# teensyMotors01.net
KiCad netlist of a schematic drawn in EAGLE
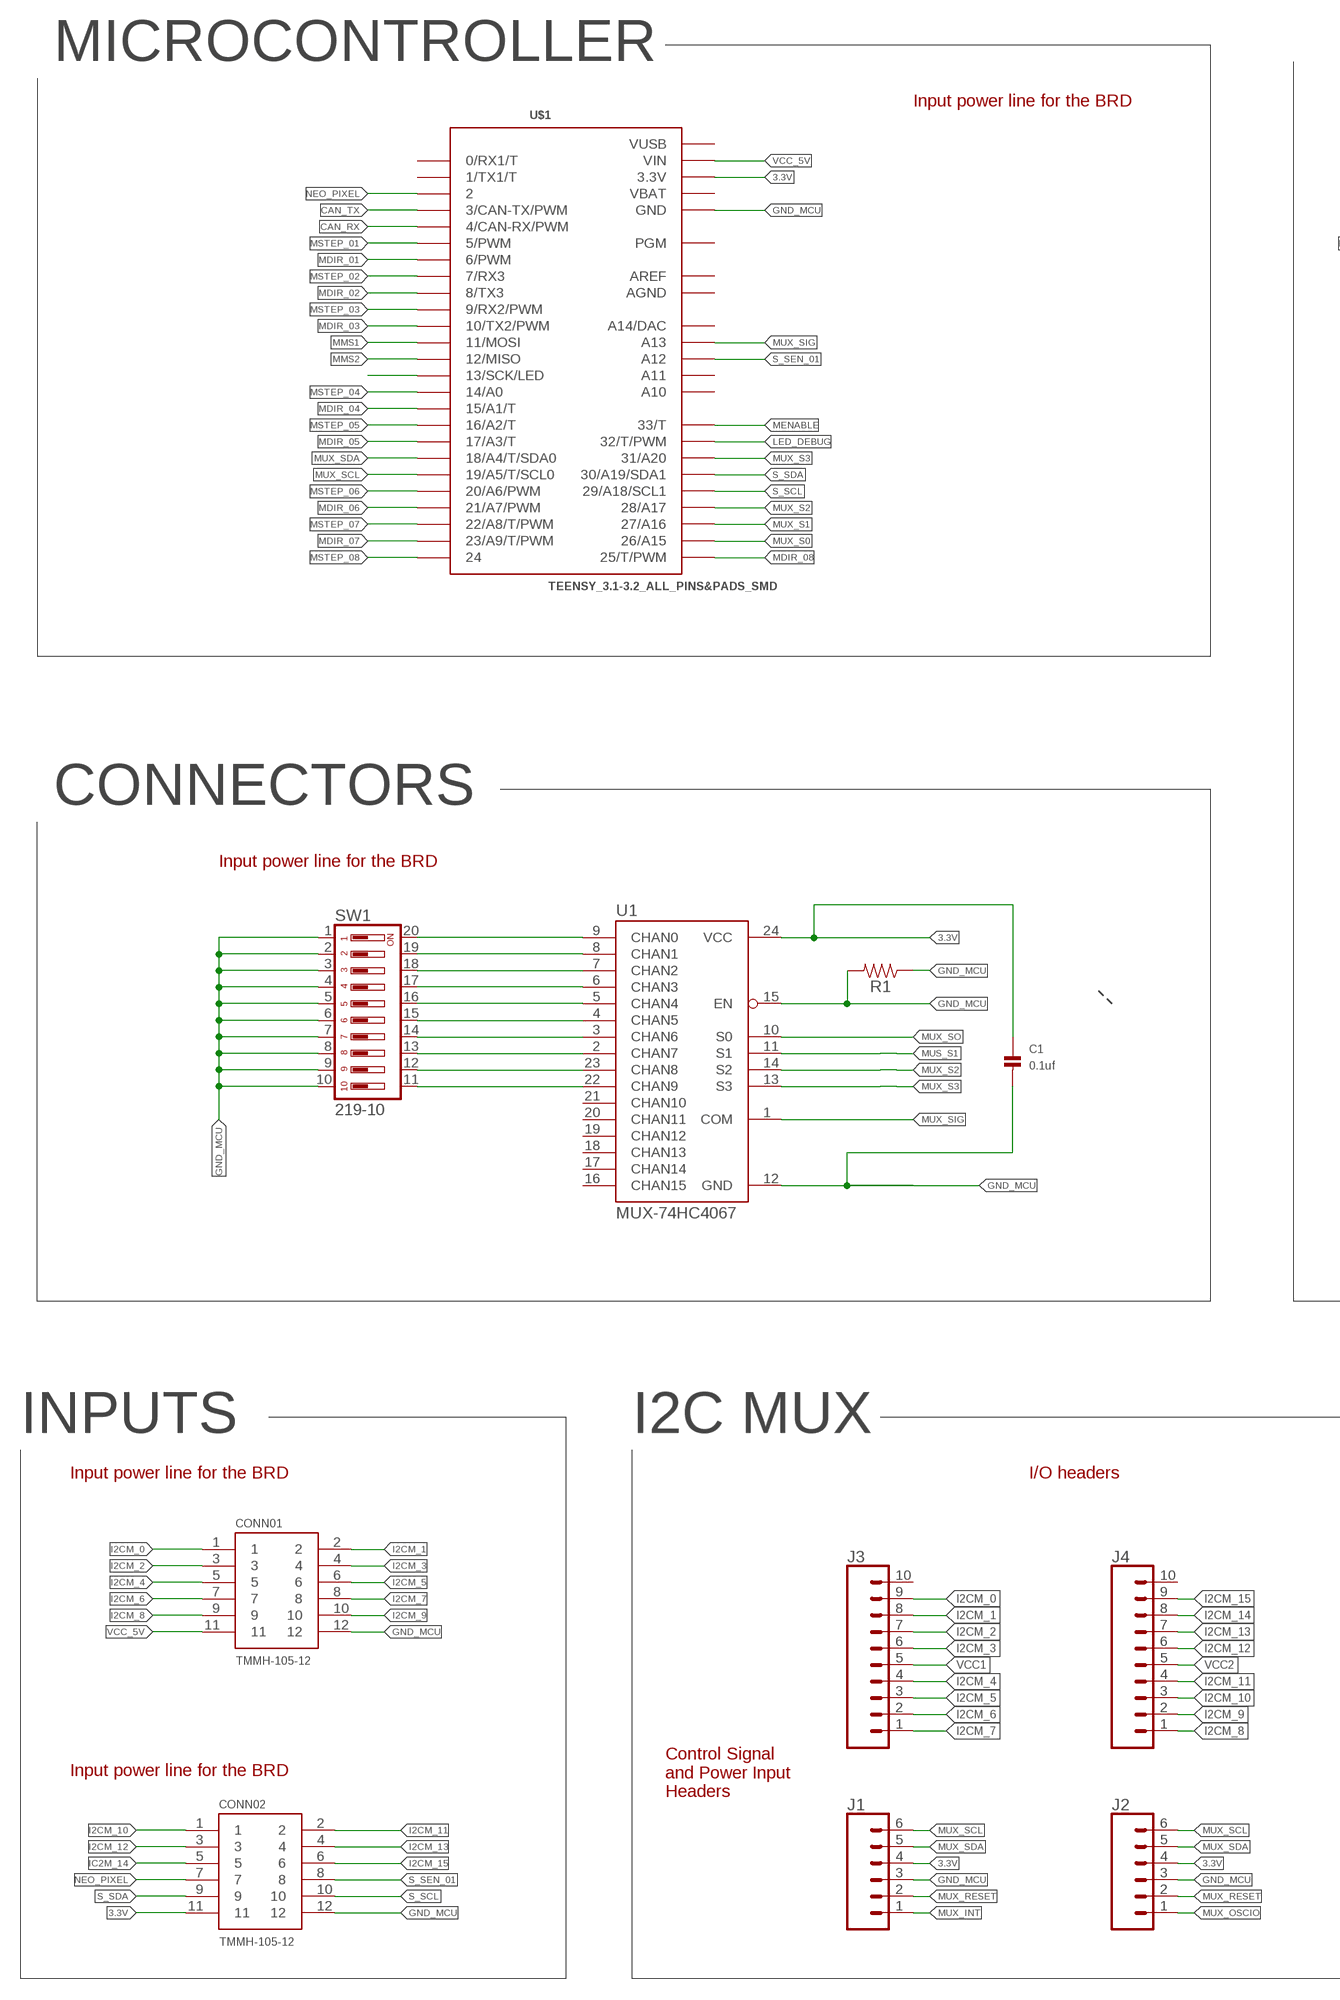
[diagram p0: schematic, sheet 1, part 1 of 2]
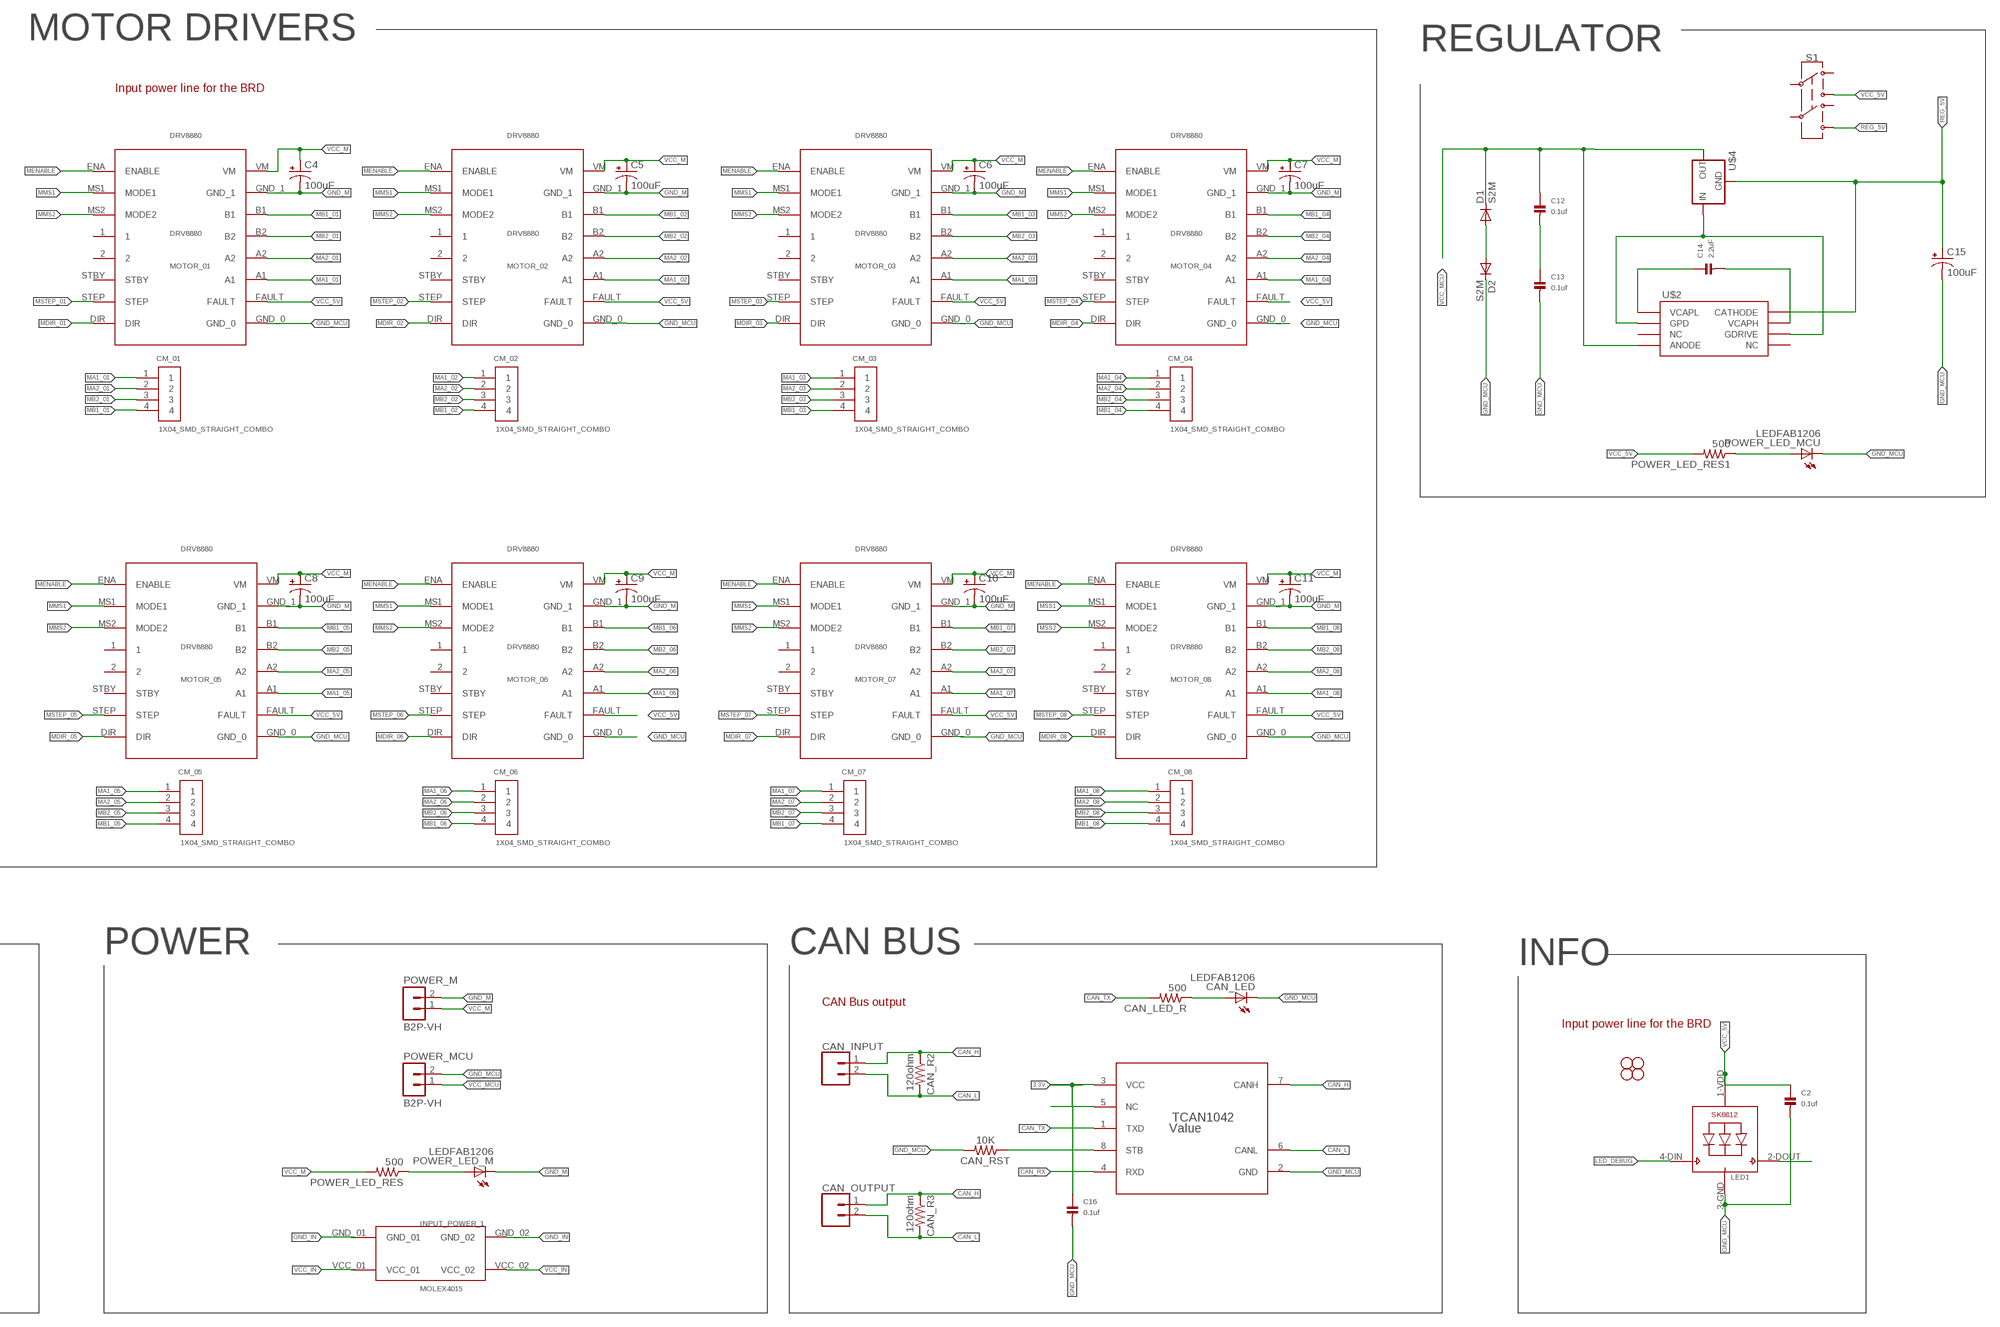
[diagram p1: schematic, sheet 1, part 2 of 2]

(export (version "E")
  (design (tool "Eeschema 10.0.6"))
  (components
    (comp (ref "C1")
      (value "0.1uf")
      (footprint "eagle-import:1206")
      (libsource (lib "eagle-import") (part "CAP_CERAMIC1206"))
    )
    (comp (ref "C2")
      (value "0.1uf")
      (footprint "eagle-import:1206")
      (libsource (lib "eagle-import") (part "CAP_CERAMIC1206"))
    )
    (comp (ref "C4")
      (value "100uF")
      (footprint "eagle-import:PANASONIC_D")
      (libsource (lib "eagle-import") (part "100UF-POLAR-25V-20%(ELEC)"))
    )
    (comp (ref "C5")
      (value "100uF")
      (footprint "eagle-import:PANASONIC_D")
      (libsource (lib "eagle-import") (part "100UF-POLAR-25V-20%(ELEC)"))
    )
    (comp (ref "C6")
      (value "100uF")
      (footprint "eagle-import:PANASONIC_D")
      (libsource (lib "eagle-import") (part "100UF-POLAR-25V-20%(ELEC)"))
    )
    (comp (ref "C7")
      (value "100uF")
      (footprint "eagle-import:PANASONIC_D")
      (libsource (lib "eagle-import") (part "100UF-POLAR-25V-20%(ELEC)"))
    )
    (comp (ref "C8")
      (value "100uF")
      (footprint "eagle-import:PANASONIC_D")
      (libsource (lib "eagle-import") (part "100UF-POLAR-25V-20%(ELEC)"))
    )
    (comp (ref "C9")
      (value "100uF")
      (footprint "eagle-import:PANASONIC_D")
      (libsource (lib "eagle-import") (part "100UF-POLAR-25V-20%(ELEC)"))
    )
    (comp (ref "C10")
      (value "100uF")
      (footprint "eagle-import:PANASONIC_D")
      (libsource (lib "eagle-import") (part "100UF-POLAR-25V-20%(ELEC)"))
    )
    (comp (ref "C11")
      (value "100uF")
      (footprint "eagle-import:PANASONIC_D")
      (libsource (lib "eagle-import") (part "100UF-POLAR-25V-20%(ELEC)"))
    )
    (comp (ref "C12")
      (value "0.1uf")
      (footprint "eagle-import:1206")
      (libsource (lib "eagle-import") (part "CAP_CERAMIC1206"))
    )
    (comp (ref "C13")
      (value "0.1uf")
      (footprint "eagle-import:1206")
      (libsource (lib "eagle-import") (part "CAP_CERAMIC1206"))
    )
    (comp (ref "C14")
      (value "2.2uF")
      (footprint "eagle-import:1206")
      (libsource (lib "eagle-import") (part "CAP_CERAMIC1206"))
    )
    (comp (ref "C15")
      (value "100uF")
      (footprint "eagle-import:PANASONIC_D")
      (libsource (lib "eagle-import") (part "100UF-POLAR-25V-20%(ELEC)"))
    )
    (comp (ref "C16")
      (value "0.1uf")
      (footprint "eagle-import:1206")
      (libsource (lib "eagle-import") (part "CAP_CERAMIC1206"))
    )
    (comp (ref "CAN_INPUT")
      (value "CONN_02-JST-2MM-SMT")
      (footprint "eagle-import:JST-2-SMD")
      (libsource (lib "eagle-import") (part "CONN_02-JST-2MM-SMT"))
    )
    (comp (ref "CAN_LED")
      (value "LEDFAB1206")
      (footprint "eagle-import:LED1206FAB")
      (libsource (lib "eagle-import") (part "LEDFAB1206"))
    )
    (comp (ref "CAN_LED_R")
      (value "500")
      (footprint "eagle-import:R1206FAB")
      (libsource (lib "eagle-import") (part "RES-US1206FAB"))
    )
    (comp (ref "CAN_OUTPUT")
      (value "CONN_02-JST-2MM-SMT")
      (footprint "eagle-import:JST-2-SMD")
      (libsource (lib "eagle-import") (part "CONN_02-JST-2MM-SMT"))
    )
    (comp (ref "CAN_R2")
      (value "120ohm")
      (footprint "eagle-import:1206")
      (libsource (lib "eagle-import") (part "RESISTOR1206"))
    )
    (comp (ref "CAN_R3")
      (value "120ohm")
      (footprint "eagle-import:1206")
      (libsource (lib "eagle-import") (part "RESISTOR1206"))
    )
    (comp (ref "CAN_RST")
      (value "10K")
      (footprint "eagle-import:1206")
      (libsource (lib "eagle-import") (part "RESISTOR1206"))
    )
    (comp (ref "CM_01")
      (value "1X04_SMD_STRAIGHT_COMBO")
      (footprint "eagle-import:1X04-CLEANBIG")
      (libsource (lib "eagle-import") (part "1X4-CLEANBIG"))
    )
    (comp (ref "CM_02")
      (value "1X04_SMD_STRAIGHT_COMBO")
      (footprint "eagle-import:1X04-CLEANBIG")
      (libsource (lib "eagle-import") (part "1X4-CLEANBIG"))
    )
    (comp (ref "CM_03")
      (value "1X04_SMD_STRAIGHT_COMBO")
      (footprint "eagle-import:1X04-CLEANBIG")
      (libsource (lib "eagle-import") (part "1X4-CLEANBIG"))
    )
    (comp (ref "CM_04")
      (value "1X04_SMD_STRAIGHT_COMBO")
      (footprint "eagle-import:1X04-CLEANBIG")
      (libsource (lib "eagle-import") (part "1X4-CLEANBIG"))
    )
    (comp (ref "CM_05")
      (value "1X04_SMD_STRAIGHT_COMBO")
      (footprint "eagle-import:1X04-CLEANBIG")
      (libsource (lib "eagle-import") (part "1X4-CLEANBIG"))
    )
    (comp (ref "CM_06")
      (value "1X04_SMD_STRAIGHT_COMBO")
      (footprint "eagle-import:1X04-CLEANBIG")
      (libsource (lib "eagle-import") (part "1X4-CLEANBIG"))
    )
    (comp (ref "CM_07")
      (value "1X04_SMD_STRAIGHT_COMBO")
      (footprint "eagle-import:1X04-CLEANBIG")
      (libsource (lib "eagle-import") (part "1X4-CLEANBIG"))
    )
    (comp (ref "CM_08")
      (value "1X04_SMD_STRAIGHT_COMBO")
      (footprint "eagle-import:1X04-CLEANBIG")
      (libsource (lib "eagle-import") (part "1X4-CLEANBIG"))
    )
    (comp (ref "CONN01")
      (value "TMMH-105-12")
      (footprint "eagle-import:TMMH-105-12")
      (libsource (lib "eagle-import") (part "TMMH-105-12"))
    )
    (comp (ref "CONN02")
      (value "TMMH-105-12")
      (footprint "eagle-import:TMMH-105-12")
      (libsource (lib "eagle-import") (part "TMMH-105-12"))
    )
    (comp (ref "D1")
      (value "S2M")
      (footprint "eagle-import:DO214AA")
      (fields (field (name "MF") "Fairchild"))
      (libsource (lib "eagle-import") (part "S2M"))
    )
    (comp (ref "D2")
      (value "S2M")
      (footprint "eagle-import:DO214AA")
      (fields (field (name "MF") "Fairchild"))
      (libsource (lib "eagle-import") (part "S2M"))
    )
    (comp (ref "INPUT_POWER_1")
      (value "MOLEX4015")
      (footprint "eagle-import:MOLEX4015")
      (libsource (lib "eagle-import") (part "MOLEX4015"))
    )
    (comp (ref "J1")
      (value "CONN_06SMD_MALE")
      (footprint "eagle-import:1X06_SMD_MALE")
      (libsource (lib "eagle-import") (part "CONN_06SMD_MALE"))
    )
    (comp (ref "J2")
      (value "CONN_06SMD_MALE")
      (footprint "eagle-import:1X06_SMD_MALE")
      (libsource (lib "eagle-import") (part "CONN_06SMD_MALE"))
    )
    (comp (ref "J3")
      (value "CONN_10SMD_MALE")
      (footprint "eagle-import:1X10_SMD_MALE")
      (libsource (lib "eagle-import") (part "CONN_10SMD_MALE"))
    )
    (comp (ref "J4")
      (value "CONN_10SMD_MALE")
      (footprint "eagle-import:1X10_SMD_MALE")
      (libsource (lib "eagle-import") (part "CONN_10SMD_MALE"))
    )
    (comp (ref "LED1")
      (value "SK6812_5050N")
      (footprint "eagle-import:LED5050_N")
      (libsource (lib "eagle-import") (part "SK6812_5050N"))
    )
    (comp (ref "MOTOR_01")
      (value "DRV8880")
      (footprint "eagle-import:DRV8880")
      (libsource (lib "eagle-import") (part "DRV8880"))
    )
    (comp (ref "MOTOR_02")
      (value "DRV8880")
      (footprint "eagle-import:DRV8880")
      (libsource (lib "eagle-import") (part "DRV8880"))
    )
    (comp (ref "MOTOR_03")
      (value "DRV8880")
      (footprint "eagle-import:DRV8880")
      (libsource (lib "eagle-import") (part "DRV8880"))
    )
    (comp (ref "MOTOR_04")
      (value "DRV8880")
      (footprint "eagle-import:DRV8880")
      (libsource (lib "eagle-import") (part "DRV8880"))
    )
    (comp (ref "MOTOR_05")
      (value "DRV8880")
      (footprint "eagle-import:DRV8880")
      (libsource (lib "eagle-import") (part "DRV8880"))
    )
    (comp (ref "MOTOR_06")
      (value "DRV8880")
      (footprint "eagle-import:DRV8880")
      (libsource (lib "eagle-import") (part "DRV8880"))
    )
    (comp (ref "MOTOR_07")
      (value "DRV8880")
      (footprint "eagle-import:DRV8880")
      (libsource (lib "eagle-import") (part "DRV8880"))
    )
    (comp (ref "MOTOR_08")
      (value "DRV8880")
      (footprint "eagle-import:DRV8880")
      (libsource (lib "eagle-import") (part "DRV8880"))
    )
    (comp (ref "POWER_LED_M")
      (value "LEDFAB1206")
      (footprint "eagle-import:LED1206FAB")
      (libsource (lib "eagle-import") (part "LEDFAB1206"))
    )
    (comp (ref "POWER_LED_MCU")
      (value "LEDFAB1206")
      (footprint "eagle-import:LED1206FAB")
      (libsource (lib "eagle-import") (part "LEDFAB1206"))
    )
    (comp (ref "POWER_LED_RES")
      (value "500")
      (footprint "eagle-import:R1206FAB")
      (libsource (lib "eagle-import") (part "RES-US1206FAB"))
    )
    (comp (ref "POWER_LED_RES1")
      (value "500")
      (footprint "eagle-import:R1206FAB")
      (libsource (lib "eagle-import") (part "RES-US1206FAB"))
    )
    (comp (ref "POWER_M")
      (value "B2P-VH")
      (footprint "eagle-import:B2P-VH")
      (libsource (lib "eagle-import") (part "B2P-VH"))
    )
    (comp (ref "POWER_MCU")
      (value "B2P-VH")
      (footprint "eagle-import:B2P-VH")
      (libsource (lib "eagle-import") (part "B2P-VH"))
    )
    (comp (ref "R1")
      (value "RESISTOR1206")
      (footprint "eagle-import:1206")
      (libsource (lib "eagle-import") (part "RESISTOR1206"))
    )
    (comp (ref "S1")
      (value "SWITCH-DPDT-SMD-AYZ0202")
      (footprint "eagle-import:SWITCH_DPDT_SMD_AYZ0202")
      (fields (field (name "SPICEPREFIX") "X"))
      (libsource (lib "eagle-import") (part "SWITCH-DPDT-SMD-AYZ0202"))
    )
    (comp (ref "STANDOFF5")
      (value "STAND-OFF")
      (footprint "eagle-import:STAND-OFF")
      (libsource (lib "eagle-import") (part "STAND-OFF"))
    )
    (comp (ref "STANDOFF6")
      (value "STAND-OFF")
      (footprint "eagle-import:STAND-OFF")
      (libsource (lib "eagle-import") (part "STAND-OFF"))
    )
    (comp (ref "STANDOFF7")
      (value "STAND-OFF")
      (footprint "eagle-import:STAND-OFF")
      (libsource (lib "eagle-import") (part "STAND-OFF"))
    )
    (comp (ref "STANDOFF8")
      (value "STAND-OFF")
      (footprint "eagle-import:STAND-OFF")
      (libsource (lib "eagle-import") (part "STAND-OFF"))
    )
    (comp (ref "SW1")
      (value "219-10")
      (footprint "eagle-import:CTS-219-10")
      (fields (field (name "MF") "SLI (CML/IDI)") (field (name "MPN") "219-10PK"))
      (libsource (lib "eagle-import") (part "219-10"))
    )
    (comp (ref "TCAN1042")
      (value "Value")
      (footprint "eagle-import:D0008A_N")
      (fields (field (name "MANUFACTURER") "Texas Instruments") (field (name "PARTNUMBER") "TCAN1042DRQ1"))
      (libsource (lib "eagle-import") (part "TCAN1042DRQ1"))
    )
    (comp (ref "U$1")
      (value "TEENSY_3.1-3.2_ALL_PINS&PADS_SMD")
      (footprint "eagle-import:TEENSY_3.0-3.2_ALL_PINS_&_PADS_SMD")
      (libsource (lib "eagle-import") (part "TEENSY_3.1-3.2_ALL_PINS&PADS_SMD"))
    )
    (comp (ref "U$2")
      (value "LM74610-Q1")
      (footprint "eagle-import:VSSOP(8)")
      (fields (field (name "MPN") "LM74610-Q1 "))
      (libsource (lib "eagle-import") (part "LM74610-Q1"))
    )
    (comp (ref "U$4")
      (value "BUK")
      (footprint "eagle-import:TO263-3")
      (libsource (lib "eagle-import") (part "BUK"))
    )
    (comp (ref "U1")
      (value "MUX-74HC4067")
      (footprint "eagle-import:SSOP24")
      (libsource (lib "eagle-import") (part "MUX-74HC4067SMD"))
    )
  )
  (nets
    (net (code "1") (name "3.3V") (class "Default")
      (node (ref "C1") (pin "1") (pinfunction "P$1_1") (pintype "passive"))
      (node (ref "C16") (pin "1") (pinfunction "P$1_1") (pintype "passive"))
      (node (ref "CONN02") (pin "11") (pinfunction "11_11") (pintype "bidirectional"))
      (node (ref "J1") (pin "4") (pinfunction "4_4") (pintype "passive"))
      (node (ref "J2") (pin "4") (pinfunction "4_4") (pintype "passive"))
      (node (ref "TCAN1042") (pin "3") (pinfunction "VCC_3") (pintype "power_in"))
      (node (ref "U$1") (pin "3.3V") (pinfunction "3.3V_3.3V") (pintype "power_in"))
      (node (ref "U$1") (pin "3.3V1") (pinfunction "3.3V_3.3V1") (pintype "power_in"))
      (node (ref "U$1") (pin "3.3V2") (pinfunction "3.3V_3.3V2") (pintype "power_in"))
      (node (ref "U1") (pin "24") (pinfunction "VCC_24") (pintype "bidirectional"))
    )
    (net (code "2") (name "AGND") (class "Default")
      (node (ref "U$1") (pin "AGND") (pinfunction "AGND_AGND") (pintype "power_in"))
    )
    (net (code "3") (name "AREF") (class "Default")
      (node (ref "U$1") (pin "AREF") (pinfunction "AREF_AREF") (pintype "power_in"))
    )
    (net (code "4") (name "CAN_H") (class "Default")
      (node (ref "CAN_INPUT") (pin "1") (pinfunction "2_1") (pintype "passive"))
      (node (ref "CAN_OUTPUT") (pin "1") (pinfunction "2_1") (pintype "passive"))
      (node (ref "CAN_R2") (pin "1") (pinfunction "1_1") (pintype "passive"))
      (node (ref "CAN_R3") (pin "1") (pinfunction "1_1") (pintype "passive"))
      (node (ref "TCAN1042") (pin "7") (pinfunction "CANH_7") (pintype "bidirectional"))
    )
    (net (code "5") (name "CAN_L") (class "Default")
      (node (ref "CAN_INPUT") (pin "2") (pinfunction "1_2") (pintype "passive"))
      (node (ref "CAN_OUTPUT") (pin "2") (pinfunction "1_2") (pintype "passive"))
      (node (ref "CAN_R2") (pin "2") (pinfunction "2_2") (pintype "passive"))
      (node (ref "CAN_R3") (pin "2") (pinfunction "2_2") (pintype "passive"))
      (node (ref "TCAN1042") (pin "6") (pinfunction "CANL_6") (pintype "bidirectional"))
    )
    (net (code "6") (name "CAN_RX") (class "Default")
      (node (ref "TCAN1042") (pin "4") (pinfunction "RXD_4") (pintype "output"))
      (node (ref "U$1") (pin "4") (pinfunction "4/CAN-RX/PWM_4") (pintype "bidirectional"))
    )
    (net (code "7") (name "CAN_TX") (class "Default")
      (node (ref "CAN_LED_R") (pin "2") (pinfunction "2_2") (pintype "passive"))
      (node (ref "TCAN1042") (pin "1") (pinfunction "TXD_1") (pintype "input"))
      (node (ref "U$1") (pin "3") (pinfunction "3/CAN-TX/PWM_3") (pintype "bidirectional"))
    )
    (net (code "8") (name "GND_IN") (class "Default")
      (node (ref "INPUT_POWER_1") (pin "GND_01") (pinfunction "GND_01_GND_01") (pintype "bidirectional"))
      (node (ref "INPUT_POWER_1") (pin "GND_02") (pinfunction "GND_02_GND_02") (pintype "bidirectional"))
    )
    (net (code "9") (name "GND_M") (class "Default")
      (node (ref "C10") (pin "-") (pinfunction "-_-") (pintype "passive"))
      (node (ref "C11") (pin "-") (pinfunction "-_-") (pintype "passive"))
      (node (ref "C4") (pin "-") (pinfunction "-_-") (pintype "passive"))
      (node (ref "C5") (pin "-") (pinfunction "-_-") (pintype "passive"))
      (node (ref "C6") (pin "-") (pinfunction "-_-") (pintype "passive"))
      (node (ref "C7") (pin "-") (pinfunction "-_-") (pintype "passive"))
      (node (ref "C8") (pin "-") (pinfunction "-_-") (pintype "passive"))
      (node (ref "C9") (pin "-") (pinfunction "-_-") (pintype "passive"))
      (node (ref "MOTOR_01") (pin "GND_1") (pinfunction "GND_1_GND_1") (pintype "bidirectional"))
      (node (ref "MOTOR_02") (pin "GND_1") (pinfunction "GND_1_GND_1") (pintype "bidirectional"))
      (node (ref "MOTOR_03") (pin "GND_1") (pinfunction "GND_1_GND_1") (pintype "bidirectional"))
      (node (ref "MOTOR_04") (pin "GND_1") (pinfunction "GND_1_GND_1") (pintype "bidirectional"))
      (node (ref "MOTOR_05") (pin "GND_1") (pinfunction "GND_1_GND_1") (pintype "bidirectional"))
      (node (ref "MOTOR_06") (pin "GND_1") (pinfunction "GND_1_GND_1") (pintype "bidirectional"))
      (node (ref "MOTOR_07") (pin "GND_1") (pinfunction "GND_1_GND_1") (pintype "bidirectional"))
      (node (ref "MOTOR_08") (pin "GND_1") (pinfunction "GND_1_GND_1") (pintype "bidirectional"))
      (node (ref "POWER_LED_M") (pin "2") (pinfunction "C_2") (pintype "passive"))
      (node (ref "POWER_M") (pin "2") (pinfunction "2_2") (pintype "passive"))
    )
    (net (code "10") (name "GND_MCU") (class "Default")
      (node (ref "C1") (pin "2") (pinfunction "P$2_2") (pintype "passive"))
      (node (ref "C13") (pin "2") (pinfunction "P$2_2") (pintype "passive"))
      (node (ref "C15") (pin "-") (pinfunction "-_-") (pintype "passive"))
      (node (ref "C16") (pin "2") (pinfunction "P$2_2") (pintype "passive"))
      (node (ref "C2") (pin "2") (pinfunction "P$2_2") (pintype "passive"))
      (node (ref "CAN_LED") (pin "2") (pinfunction "C_2") (pintype "passive"))
      (node (ref "CAN_RST") (pin "2") (pinfunction "2_2") (pintype "passive"))
      (node (ref "CONN01") (pin "12") (pinfunction "12_12") (pintype "bidirectional"))
      (node (ref "CONN02") (pin "12") (pinfunction "12_12") (pintype "bidirectional"))
      (node (ref "D2") (pin "C") (pinfunction "C_C") (pintype "passive"))
      (node (ref "J1") (pin "3") (pinfunction "3_3") (pintype "passive"))
      (node (ref "J2") (pin "3") (pinfunction "3_3") (pintype "passive"))
      (node (ref "LED1") (pin "3-GND") (pinfunction "GND_3-GND") (pintype "power_in"))
      (node (ref "MOTOR_01") (pin "GND_0") (pinfunction "GND_0_GND_0") (pintype "bidirectional"))
      (node (ref "MOTOR_02") (pin "GND_0") (pinfunction "GND_0_GND_0") (pintype "bidirectional"))
      (node (ref "MOTOR_03") (pin "GND_0") (pinfunction "GND_0_GND_0") (pintype "bidirectional"))
      (node (ref "MOTOR_04") (pin "GND_0") (pinfunction "GND_0_GND_0") (pintype "bidirectional"))
      (node (ref "MOTOR_05") (pin "GND_0") (pinfunction "GND_0_GND_0") (pintype "bidirectional"))
      (node (ref "MOTOR_06") (pin "GND_0") (pinfunction "GND_0_GND_0") (pintype "bidirectional"))
      (node (ref "MOTOR_07") (pin "GND_0") (pinfunction "GND_0_GND_0") (pintype "bidirectional"))
      (node (ref "MOTOR_08") (pin "GND_0") (pinfunction "GND_0_GND_0") (pintype "bidirectional"))
      (node (ref "POWER_LED_MCU") (pin "2") (pinfunction "C_2") (pintype "passive"))
      (node (ref "POWER_MCU") (pin "2") (pinfunction "2_2") (pintype "passive"))
      (node (ref "R1") (pin "1") (pinfunction "1_1") (pintype "passive"))
      (node (ref "R1") (pin "2") (pinfunction "2_2") (pintype "passive"))
      (node (ref "SW1") (pin "1") (pinfunction "1_1") (pintype "passive"))
      (node (ref "SW1") (pin "10") (pinfunction "10_10") (pintype "passive"))
      (node (ref "SW1") (pin "2") (pinfunction "2_2") (pintype "passive"))
      (node (ref "SW1") (pin "3") (pinfunction "3_3") (pintype "passive"))
      (node (ref "SW1") (pin "4") (pinfunction "4_4") (pintype "passive"))
      (node (ref "SW1") (pin "5") (pinfunction "5_5") (pintype "passive"))
      (node (ref "SW1") (pin "6") (pinfunction "6_6") (pintype "passive"))
      (node (ref "SW1") (pin "7") (pinfunction "7_7") (pintype "passive"))
      (node (ref "SW1") (pin "8") (pinfunction "8_8") (pintype "passive"))
      (node (ref "SW1") (pin "9") (pinfunction "9_9") (pintype "passive"))
      (node (ref "TCAN1042") (pin "2") (pinfunction "GND_2") (pintype "power_in"))
      (node (ref "U$1") (pin "GND") (pinfunction "GND_GND") (pintype "power_in"))
      (node (ref "U$1") (pin "GND1") (pinfunction "GND_GND1") (pintype "power_in"))
      (node (ref "U$1") (pin "GND2") (pinfunction "GND_GND2") (pintype "power_in"))
      (node (ref "U1") (pin "12") (pinfunction "GND_12") (pintype "bidirectional"))
      (node (ref "U1") (pin "15") (pinfunction "EN_15") (pintype "input"))
    )
    (net (code "11") (name "I2CM_0") (class "Default")
      (node (ref "CONN01") (pin "1") (pinfunction "1_1") (pintype "bidirectional"))
      (node (ref "J3") (pin "9") (pinfunction "9_9") (pintype "passive"))
    )
    (net (code "12") (name "I2CM_1") (class "Default")
      (node (ref "CONN01") (pin "2") (pinfunction "2_2") (pintype "bidirectional"))
      (node (ref "J3") (pin "8") (pinfunction "8_8") (pintype "passive"))
    )
    (net (code "13") (name "I2CM_2") (class "Default")
      (node (ref "CONN01") (pin "3") (pinfunction "3_3") (pintype "bidirectional"))
      (node (ref "J3") (pin "7") (pinfunction "7_7") (pintype "passive"))
    )
    (net (code "14") (name "I2CM_3") (class "Default")
      (node (ref "CONN01") (pin "4") (pinfunction "4_4") (pintype "bidirectional"))
      (node (ref "J3") (pin "6") (pinfunction "6_6") (pintype "passive"))
    )
    (net (code "15") (name "I2CM_4") (class "Default")
      (node (ref "CONN01") (pin "5") (pinfunction "5_5") (pintype "bidirectional"))
      (node (ref "J3") (pin "4") (pinfunction "4_4") (pintype "passive"))
    )
    (net (code "16") (name "I2CM_5") (class "Default")
      (node (ref "CONN01") (pin "6") (pinfunction "6_6") (pintype "bidirectional"))
      (node (ref "J3") (pin "3") (pinfunction "3_3") (pintype "passive"))
    )
    (net (code "17") (name "I2CM_6") (class "Default")
      (node (ref "CONN01") (pin "7") (pinfunction "7_7") (pintype "bidirectional"))
      (node (ref "J3") (pin "2") (pinfunction "2_2") (pintype "passive"))
    )
    (net (code "18") (name "I2CM_7") (class "Default")
      (node (ref "CONN01") (pin "8") (pinfunction "8_8") (pintype "bidirectional"))
      (node (ref "J3") (pin "1") (pinfunction "1_1") (pintype "passive"))
    )
    (net (code "19") (name "I2CM_8") (class "Default")
      (node (ref "CONN01") (pin "9") (pinfunction "9_9") (pintype "bidirectional"))
      (node (ref "J4") (pin "1") (pinfunction "1_1") (pintype "passive"))
    )
    (net (code "20") (name "I2CM_9") (class "Default")
      (node (ref "CONN01") (pin "10") (pinfunction "10_10") (pintype "bidirectional"))
      (node (ref "J4") (pin "2") (pinfunction "2_2") (pintype "passive"))
    )
    (net (code "21") (name "I2CM_10") (class "Default")
      (node (ref "CONN02") (pin "1") (pinfunction "1_1") (pintype "bidirectional"))
      (node (ref "J4") (pin "3") (pinfunction "3_3") (pintype "passive"))
    )
    (net (code "22") (name "I2CM_11") (class "Default")
      (node (ref "CONN02") (pin "2") (pinfunction "2_2") (pintype "bidirectional"))
      (node (ref "J4") (pin "4") (pinfunction "4_4") (pintype "passive"))
    )
    (net (code "23") (name "I2CM_12") (class "Default")
      (node (ref "CONN02") (pin "3") (pinfunction "3_3") (pintype "bidirectional"))
      (node (ref "J4") (pin "6") (pinfunction "6_6") (pintype "passive"))
    )
    (net (code "24") (name "I2CM_13") (class "Default")
      (node (ref "CONN02") (pin "4") (pinfunction "4_4") (pintype "bidirectional"))
      (node (ref "J4") (pin "7") (pinfunction "7_7") (pintype "passive"))
    )
    (net (code "25") (name "I2CM_14") (class "Default")
      (node (ref "J4") (pin "8") (pinfunction "8_8") (pintype "passive"))
    )
    (net (code "26") (name "I2CM_15") (class "Default")
      (node (ref "CONN02") (pin "6") (pinfunction "6_6") (pintype "bidirectional"))
      (node (ref "J4") (pin "9") (pinfunction "9_9") (pintype "passive"))
    )
    (net (code "27") (name "IC2M_14") (class "Default")
      (node (ref "CONN02") (pin "5") (pinfunction "5_5") (pintype "bidirectional"))
    )
    (net (code "28") (name "LED_DEBUG") (class "Default")
      (node (ref "LED1") (pin "4-DIN") (pinfunction "DI_4-DIN") (pintype "input"))
      (node (ref "U$1") (pin "32") (pinfunction "32/T/PWM_32") (pintype "bidirectional"))
    )
    (net (code "29") (name "MA1_01") (class "Default")
      (node (ref "CM_01") (pin "1") (pinfunction "1_1") (pintype "bidirectional"))
      (node (ref "MOTOR_01") (pin "A1") (pinfunction "A1_A1") (pintype "bidirectional"))
    )
    (net (code "30") (name "MA1_02") (class "Default")
      (node (ref "CM_02") (pin "1") (pinfunction "1_1") (pintype "bidirectional"))
      (node (ref "MOTOR_02") (pin "A1") (pinfunction "A1_A1") (pintype "bidirectional"))
    )
    (net (code "31") (name "MA1_03") (class "Default")
      (node (ref "CM_03") (pin "1") (pinfunction "1_1") (pintype "bidirectional"))
      (node (ref "MOTOR_03") (pin "A1") (pinfunction "A1_A1") (pintype "bidirectional"))
    )
    (net (code "32") (name "MA1_04") (class "Default")
      (node (ref "CM_04") (pin "1") (pinfunction "1_1") (pintype "bidirectional"))
      (node (ref "MOTOR_04") (pin "A1") (pinfunction "A1_A1") (pintype "bidirectional"))
    )
    (net (code "33") (name "MA1_05") (class "Default")
      (node (ref "CM_05") (pin "1") (pinfunction "1_1") (pintype "bidirectional"))
      (node (ref "MOTOR_05") (pin "A1") (pinfunction "A1_A1") (pintype "bidirectional"))
    )
    (net (code "34") (name "MA1_06") (class "Default")
      (node (ref "CM_06") (pin "1") (pinfunction "1_1") (pintype "bidirectional"))
      (node (ref "MOTOR_06") (pin "A1") (pinfunction "A1_A1") (pintype "bidirectional"))
    )
    (net (code "35") (name "MA1_07") (class "Default")
      (node (ref "CM_07") (pin "1") (pinfunction "1_1") (pintype "bidirectional"))
      (node (ref "MOTOR_07") (pin "A1") (pinfunction "A1_A1") (pintype "bidirectional"))
    )
    (net (code "36") (name "MA1_08") (class "Default")
      (node (ref "CM_08") (pin "1") (pinfunction "1_1") (pintype "bidirectional"))
      (node (ref "MOTOR_08") (pin "A1") (pinfunction "A1_A1") (pintype "bidirectional"))
    )
    (net (code "37") (name "MA2_01") (class "Default")
      (node (ref "CM_01") (pin "2") (pinfunction "2_2") (pintype "bidirectional"))
      (node (ref "MOTOR_01") (pin "A2") (pinfunction "A2_A2") (pintype "bidirectional"))
    )
    (net (code "38") (name "MA2_02") (class "Default")
      (node (ref "CM_02") (pin "2") (pinfunction "2_2") (pintype "bidirectional"))
      (node (ref "MOTOR_02") (pin "A2") (pinfunction "A2_A2") (pintype "bidirectional"))
    )
    (net (code "39") (name "MA2_03") (class "Default")
      (node (ref "CM_03") (pin "2") (pinfunction "2_2") (pintype "bidirectional"))
      (node (ref "MOTOR_03") (pin "A2") (pinfunction "A2_A2") (pintype "bidirectional"))
    )
    (net (code "40") (name "MA2_04") (class "Default")
      (node (ref "CM_04") (pin "2") (pinfunction "2_2") (pintype "bidirectional"))
      (node (ref "MOTOR_04") (pin "A2") (pinfunction "A2_A2") (pintype "bidirectional"))
    )
    (net (code "41") (name "MA2_05") (class "Default")
      (node (ref "CM_05") (pin "2") (pinfunction "2_2") (pintype "bidirectional"))
      (node (ref "MOTOR_05") (pin "A2") (pinfunction "A2_A2") (pintype "bidirectional"))
    )
    (net (code "42") (name "MA2_06") (class "Default")
      (node (ref "CM_06") (pin "2") (pinfunction "2_2") (pintype "bidirectional"))
      (node (ref "MOTOR_06") (pin "A2") (pinfunction "A2_A2") (pintype "bidirectional"))
    )
    (net (code "43") (name "MA2_07") (class "Default")
      (node (ref "CM_07") (pin "2") (pinfunction "2_2") (pintype "bidirectional"))
      (node (ref "MOTOR_07") (pin "A2") (pinfunction "A2_A2") (pintype "bidirectional"))
    )
    (net (code "44") (name "MA2_08") (class "Default")
      (node (ref "CM_08") (pin "2") (pinfunction "2_2") (pintype "bidirectional"))
      (node (ref "MOTOR_08") (pin "A2") (pinfunction "A2_A2") (pintype "bidirectional"))
    )
    (net (code "45") (name "MB1_01") (class "Default")
      (node (ref "CM_01") (pin "4") (pinfunction "4_4") (pintype "bidirectional"))
      (node (ref "MOTOR_01") (pin "B1") (pinfunction "B1_B1") (pintype "bidirectional"))
    )
    (net (code "46") (name "MB1_02") (class "Default")
      (node (ref "CM_02") (pin "4") (pinfunction "4_4") (pintype "bidirectional"))
      (node (ref "MOTOR_02") (pin "B1") (pinfunction "B1_B1") (pintype "bidirectional"))
    )
    (net (code "47") (name "MB1_03") (class "Default")
      (node (ref "CM_03") (pin "4") (pinfunction "4_4") (pintype "bidirectional"))
      (node (ref "MOTOR_03") (pin "B1") (pinfunction "B1_B1") (pintype "bidirectional"))
    )
    (net (code "48") (name "MB1_04") (class "Default")
      (node (ref "CM_04") (pin "4") (pinfunction "4_4") (pintype "bidirectional"))
      (node (ref "MOTOR_04") (pin "B1") (pinfunction "B1_B1") (pintype "bidirectional"))
    )
    (net (code "49") (name "MB1_05") (class "Default")
      (node (ref "CM_05") (pin "4") (pinfunction "4_4") (pintype "bidirectional"))
      (node (ref "MOTOR_05") (pin "B1") (pinfunction "B1_B1") (pintype "bidirectional"))
    )
    (net (code "50") (name "MB1_06") (class "Default")
      (node (ref "CM_06") (pin "4") (pinfunction "4_4") (pintype "bidirectional"))
      (node (ref "MOTOR_06") (pin "B1") (pinfunction "B1_B1") (pintype "bidirectional"))
    )
    (net (code "51") (name "MB1_07") (class "Default")
      (node (ref "CM_07") (pin "4") (pinfunction "4_4") (pintype "bidirectional"))
      (node (ref "MOTOR_07") (pin "B1") (pinfunction "B1_B1") (pintype "bidirectional"))
    )
    (net (code "52") (name "MB1_08") (class "Default")
      (node (ref "CM_08") (pin "4") (pinfunction "4_4") (pintype "bidirectional"))
      (node (ref "MOTOR_08") (pin "B1") (pinfunction "B1_B1") (pintype "bidirectional"))
    )
    (net (code "53") (name "MB2_01") (class "Default")
      (node (ref "CM_01") (pin "3") (pinfunction "3_3") (pintype "bidirectional"))
      (node (ref "MOTOR_01") (pin "B2") (pinfunction "B2_B2") (pintype "bidirectional"))
    )
    (net (code "54") (name "MB2_02") (class "Default")
      (node (ref "CM_02") (pin "3") (pinfunction "3_3") (pintype "bidirectional"))
      (node (ref "MOTOR_02") (pin "B2") (pinfunction "B2_B2") (pintype "bidirectional"))
    )
    (net (code "55") (name "MB2_03") (class "Default")
      (node (ref "CM_03") (pin "3") (pinfunction "3_3") (pintype "bidirectional"))
      (node (ref "MOTOR_03") (pin "B2") (pinfunction "B2_B2") (pintype "bidirectional"))
    )
    (net (code "56") (name "MB2_04") (class "Default")
      (node (ref "CM_04") (pin "3") (pinfunction "3_3") (pintype "bidirectional"))
      (node (ref "MOTOR_04") (pin "B2") (pinfunction "B2_B2") (pintype "bidirectional"))
    )
    (net (code "57") (name "MB2_05") (class "Default")
      (node (ref "CM_05") (pin "3") (pinfunction "3_3") (pintype "bidirectional"))
      (node (ref "MOTOR_05") (pin "B2") (pinfunction "B2_B2") (pintype "bidirectional"))
    )
    (net (code "58") (name "MB2_06") (class "Default")
      (node (ref "CM_06") (pin "3") (pinfunction "3_3") (pintype "bidirectional"))
      (node (ref "MOTOR_06") (pin "B2") (pinfunction "B2_B2") (pintype "bidirectional"))
    )
    (net (code "59") (name "MB2_07") (class "Default")
      (node (ref "CM_07") (pin "3") (pinfunction "3_3") (pintype "bidirectional"))
      (node (ref "MOTOR_07") (pin "B2") (pinfunction "B2_B2") (pintype "bidirectional"))
    )
    (net (code "60") (name "MB2_08") (class "Default")
      (node (ref "CM_08") (pin "3") (pinfunction "3_3") (pintype "bidirectional"))
      (node (ref "MOTOR_08") (pin "B2") (pinfunction "B2_B2") (pintype "bidirectional"))
    )
    (net (code "61") (name "MDIR_01") (class "Default")
      (node (ref "MOTOR_01") (pin "DIR") (pinfunction "DIR_DIR") (pintype "bidirectional"))
      (node (ref "U$1") (pin "6") (pinfunction "6/PWM_6") (pintype "bidirectional"))
    )
    (net (code "62") (name "MDIR_02") (class "Default")
      (node (ref "MOTOR_02") (pin "DIR") (pinfunction "DIR_DIR") (pintype "bidirectional"))
      (node (ref "U$1") (pin "8") (pinfunction "8/TX3_8") (pintype "bidirectional"))
    )
    (net (code "63") (name "MDIR_03") (class "Default")
      (node (ref "MOTOR_03") (pin "DIR") (pinfunction "DIR_DIR") (pintype "bidirectional"))
      (node (ref "U$1") (pin "10") (pinfunction "10/TX2/PWM_10") (pintype "bidirectional"))
    )
    (net (code "64") (name "MDIR_04") (class "Default")
      (node (ref "MOTOR_04") (pin "DIR") (pinfunction "DIR_DIR") (pintype "bidirectional"))
      (node (ref "U$1") (pin "15/A1") (pinfunction "15/A1/T_15/A1") (pintype "bidirectional"))
    )
    (net (code "65") (name "MDIR_05") (class "Default")
      (node (ref "MOTOR_05") (pin "DIR") (pinfunction "DIR_DIR") (pintype "bidirectional"))
      (node (ref "U$1") (pin "17/A3") (pinfunction "17/A3/T_17/A3") (pintype "bidirectional"))
    )
    (net (code "66") (name "MDIR_06") (class "Default")
      (node (ref "MOTOR_06") (pin "DIR") (pinfunction "DIR_DIR") (pintype "bidirectional"))
      (node (ref "U$1") (pin "21/A7") (pinfunction "21/A7/PWM_21/A7") (pintype "bidirectional"))
    )
    (net (code "67") (name "MDIR_07") (class "Default")
      (node (ref "MOTOR_07") (pin "DIR") (pinfunction "DIR_DIR") (pintype "bidirectional"))
      (node (ref "U$1") (pin "23/A9") (pinfunction "23/A9/T/PWM_23/A9") (pintype "bidirectional"))
    )
    (net (code "68") (name "MDIR_08") (class "Default")
      (node (ref "MOTOR_08") (pin "DIR") (pinfunction "DIR_DIR") (pintype "bidirectional"))
      (node (ref "U$1") (pin "25") (pinfunction "25/T/PWM_25") (pintype "bidirectional"))
    )
    (net (code "69") (name "MENABLE") (class "Default")
      (node (ref "MOTOR_01") (pin "ENA") (pinfunction "ENABLE_ENA") (pintype "bidirectional"))
      (node (ref "MOTOR_02") (pin "ENA") (pinfunction "ENABLE_ENA") (pintype "bidirectional"))
      (node (ref "MOTOR_03") (pin "ENA") (pinfunction "ENABLE_ENA") (pintype "bidirectional"))
      (node (ref "MOTOR_04") (pin "ENA") (pinfunction "ENABLE_ENA") (pintype "bidirectional"))
      (node (ref "MOTOR_05") (pin "ENA") (pinfunction "ENABLE_ENA") (pintype "bidirectional"))
      (node (ref "MOTOR_06") (pin "ENA") (pinfunction "ENABLE_ENA") (pintype "bidirectional"))
      (node (ref "MOTOR_07") (pin "ENA") (pinfunction "ENABLE_ENA") (pintype "bidirectional"))
      (node (ref "MOTOR_08") (pin "ENA") (pinfunction "ENABLE_ENA") (pintype "bidirectional"))
      (node (ref "U$1") (pin "33") (pinfunction "33/T_33") (pintype "bidirectional"))
    )
    (net (code "70") (name "MMS1") (class "Default")
      (node (ref "MOTOR_01") (pin "MS1") (pinfunction "MODE1_MS1") (pintype "bidirectional"))
      (node (ref "MOTOR_02") (pin "MS1") (pinfunction "MODE1_MS1") (pintype "bidirectional"))
      (node (ref "MOTOR_03") (pin "MS1") (pinfunction "MODE1_MS1") (pintype "bidirectional"))
      (node (ref "MOTOR_04") (pin "MS1") (pinfunction "MODE1_MS1") (pintype "bidirectional"))
      (node (ref "MOTOR_05") (pin "MS1") (pinfunction "MODE1_MS1") (pintype "bidirectional"))
      (node (ref "MOTOR_06") (pin "MS1") (pinfunction "MODE1_MS1") (pintype "bidirectional"))
      (node (ref "MOTOR_07") (pin "MS1") (pinfunction "MODE1_MS1") (pintype "bidirectional"))
      (node (ref "U$1") (pin "11") (pinfunction "11/MOSI_11") (pintype "bidirectional"))
    )
    (net (code "71") (name "MMS2") (class "Default")
      (node (ref "MOTOR_01") (pin "MS2") (pinfunction "MODE2_MS2") (pintype "bidirectional"))
      (node (ref "MOTOR_02") (pin "MS2") (pinfunction "MODE2_MS2") (pintype "bidirectional"))
      (node (ref "MOTOR_03") (pin "MS2") (pinfunction "MODE2_MS2") (pintype "bidirectional"))
      (node (ref "MOTOR_04") (pin "MS2") (pinfunction "MODE2_MS2") (pintype "bidirectional"))
      (node (ref "MOTOR_05") (pin "MS2") (pinfunction "MODE2_MS2") (pintype "bidirectional"))
      (node (ref "MOTOR_06") (pin "MS2") (pinfunction "MODE2_MS2") (pintype "bidirectional"))
      (node (ref "MOTOR_07") (pin "MS2") (pinfunction "MODE2_MS2") (pintype "bidirectional"))
      (node (ref "U$1") (pin "12") (pinfunction "12/MISO_12") (pintype "bidirectional"))
    )
    (net (code "72") (name "MSS1") (class "Default")
      (node (ref "MOTOR_08") (pin "MS1") (pinfunction "MODE1_MS1") (pintype "bidirectional"))
    )
    (net (code "73") (name "MSS2") (class "Default")
      (node (ref "MOTOR_08") (pin "MS2") (pinfunction "MODE2_MS2") (pintype "bidirectional"))
    )
    (net (code "74") (name "MSTEP_01") (class "Default")
      (node (ref "MOTOR_01") (pin "STEP") (pinfunction "STEP_STEP") (pintype "bidirectional"))
      (node (ref "U$1") (pin "5") (pinfunction "5/PWM_5") (pintype "bidirectional"))
    )
    (net (code "75") (name "MSTEP_02") (class "Default")
      (node (ref "MOTOR_02") (pin "STEP") (pinfunction "STEP_STEP") (pintype "bidirectional"))
      (node (ref "U$1") (pin "7") (pinfunction "7/RX3_7") (pintype "bidirectional"))
    )
    (net (code "76") (name "MSTEP_03") (class "Default")
      (node (ref "MOTOR_03") (pin "STEP") (pinfunction "STEP_STEP") (pintype "bidirectional"))
      (node (ref "U$1") (pin "9") (pinfunction "9/RX2/PWM_9") (pintype "bidirectional"))
    )
    (net (code "77") (name "MSTEP_04") (class "Default")
      (node (ref "MOTOR_04") (pin "STEP") (pinfunction "STEP_STEP") (pintype "bidirectional"))
      (node (ref "U$1") (pin "14/A0") (pinfunction "14/A0_14/A0") (pintype "bidirectional"))
    )
    (net (code "78") (name "MSTEP_05") (class "Default")
      (node (ref "MOTOR_05") (pin "STEP") (pinfunction "STEP_STEP") (pintype "bidirectional"))
      (node (ref "U$1") (pin "16/A2") (pinfunction "16/A2/T_16/A2") (pintype "bidirectional"))
    )
    (net (code "79") (name "MSTEP_06") (class "Default")
      (node (ref "MOTOR_06") (pin "STEP") (pinfunction "STEP_STEP") (pintype "bidirectional"))
      (node (ref "U$1") (pin "20/A6") (pinfunction "20/A6/PWM_20/A6") (pintype "bidirectional"))
    )
    (net (code "80") (name "MSTEP_07") (class "Default")
      (node (ref "MOTOR_07") (pin "STEP") (pinfunction "STEP_STEP") (pintype "bidirectional"))
      (node (ref "U$1") (pin "22/A8") (pinfunction "22/A8/T/PWM_22/A8") (pintype "bidirectional"))
    )
    (net (code "81") (name "MSTEP_08") (class "Default")
      (node (ref "MOTOR_08") (pin "STEP") (pinfunction "STEP_STEP") (pintype "bidirectional"))
      (node (ref "U$1") (pin "24") (pinfunction "24_24") (pintype "bidirectional"))
    )
    (net (code "82") (name "MUS_S1") (class "Default")
      (node (ref "U1") (pin "11") (pinfunction "S1_11") (pintype "input"))
    )
    (net (code "83") (name "MUX_INT") (class "Default")
      (node (ref "J1") (pin "1") (pinfunction "1_1") (pintype "passive"))
    )
    (net (code "84") (name "MUX_OSCIO") (class "Default")
      (node (ref "J2") (pin "1") (pinfunction "1_1") (pintype "passive"))
    )
    (net (code "85") (name "MUX_RESET") (class "Default")
      (node (ref "J1") (pin "2") (pinfunction "2_2") (pintype "passive"))
      (node (ref "J2") (pin "2") (pinfunction "2_2") (pintype "passive"))
    )
    (net (code "86") (name "MUX_S0") (class "Default")
      (node (ref "U$1") (pin "26") (pinfunction "26/A15_26") (pintype "bidirectional"))
    )
    (net (code "87") (name "MUX_S1") (class "Default")
      (node (ref "U$1") (pin "27") (pinfunction "27/A16_27") (pintype "bidirectional"))
    )
    (net (code "88") (name "MUX_S2") (class "Default")
      (node (ref "U$1") (pin "28") (pinfunction "28/A17_28") (pintype "bidirectional"))
      (node (ref "U1") (pin "14") (pinfunction "S2_14") (pintype "input"))
    )
    (net (code "89") (name "MUX_S3") (class "Default")
      (node (ref "U$1") (pin "31") (pinfunction "31/A20_31") (pintype "bidirectional"))
      (node (ref "U1") (pin "13") (pinfunction "S3_13") (pintype "input"))
    )
    (net (code "90") (name "MUX_SCL") (class "Default")
      (node (ref "J1") (pin "6") (pinfunction "6_6") (pintype "passive"))
      (node (ref "J2") (pin "6") (pinfunction "6_6") (pintype "passive"))
      (node (ref "U$1") (pin "19/A5") (pinfunction "19/A5/T/SCL0_19/A5") (pintype "bidirectional"))
    )
    (net (code "91") (name "MUX_SDA") (class "Default")
      (node (ref "J1") (pin "5") (pinfunction "5_5") (pintype "passive"))
      (node (ref "J2") (pin "5") (pinfunction "5_5") (pintype "passive"))
      (node (ref "U$1") (pin "18/A4") (pinfunction "18/A4/T/SDA0_18/A4") (pintype "bidirectional"))
    )
    (net (code "92") (name "MUX_SIG") (class "Default")
      (node (ref "U$1") (pin "A13") (pinfunction "A13_A13") (pintype "bidirectional"))
      (node (ref "U1") (pin "1") (pinfunction "COM_1") (pintype "bidirectional"))
    )
    (net (code "93") (name "MUX_SO") (class "Default")
      (node (ref "U1") (pin "10") (pinfunction "S0_10") (pintype "input"))
    )
    (net (code "94") (name "NEO_PIXEL") (class "Default")
      (node (ref "CONN02") (pin "7") (pinfunction "7_7") (pintype "bidirectional"))
      (node (ref "U$1") (pin "2") (pinfunction "2_2") (pintype "bidirectional"))
    )
    (net (code "95") (name "Net-(C12-P$2)") (class "Default")
      (node (ref "C12") (pin "2") (pinfunction "P$2_2") (pintype "passive"))
      (node (ref "C13") (pin "1") (pinfunction "P$1_1") (pintype "passive"))
    )
    (net (code "96") (name "Net-(C14-P$1)") (class "Default")
      (node (ref "C14") (pin "1") (pinfunction "P$1_1") (pintype "passive"))
      (node (ref "U$2") (pin "VCAPL") (pinfunction "VCAPL_VCAPL") (pintype "bidirectional"))
    )
    (net (code "97") (name "Net-(C14-P$2)") (class "Default")
      (node (ref "C14") (pin "2") (pinfunction "P$2_2") (pintype "passive"))
      (node (ref "U$2") (pin "VCAPH") (pinfunction "VCAPH_VCAPH") (pintype "bidirectional"))
    )
    (net (code "98") (name "Net-(CAN_LED-A)") (class "Default")
      (node (ref "CAN_LED") (pin "1") (pinfunction "A_1") (pintype "passive"))
      (node (ref "CAN_LED_R") (pin "1") (pinfunction "1_1") (pintype "passive"))
    )
    (net (code "99") (name "Net-(D1-PadA)") (class "Default")
      (node (ref "D1") (pin "A") (pinfunction "A_A") (pintype "passive"))
      (node (ref "D2") (pin "A") (pinfunction "A_A") (pintype "passive"))
    )
    (net (code "100") (name "Net-(POWER_LED_M-A)") (class "Default")
      (node (ref "POWER_LED_M") (pin "1") (pinfunction "A_1") (pintype "passive"))
      (node (ref "POWER_LED_RES") (pin "1") (pinfunction "1_1") (pintype "passive"))
    )
    (net (code "101") (name "Net-(POWER_LED_MCU-A)") (class "Default")
      (node (ref "POWER_LED_MCU") (pin "1") (pinfunction "A_1") (pintype "passive"))
      (node (ref "POWER_LED_RES1") (pin "1") (pinfunction "1_1") (pintype "passive"))
    )
    (net (code "102") (name "Net-(TCAN1042-STB)") (class "Default")
      (node (ref "CAN_RST") (pin "1") (pinfunction "1_1") (pintype "passive"))
      (node (ref "TCAN1042") (pin "8") (pinfunction "STB_8") (pintype "input"))
    )
    (net (code "103") (name "Net-(U$4-IN)") (class "Default")
      (node (ref "U$2") (pin "GDRIVE") (pinfunction "GDRIVE_GDRIVE") (pintype "bidirectional"))
      (node (ref "U$2") (pin "GPD") (pinfunction "GPD_GPD") (pintype "bidirectional"))
      (node (ref "U$4") (pin "1") (pinfunction "IN_1") (pintype "input"))
    )
    (net (code "104") (name "Net-(U1-CHAN0)") (class "Default")
      (node (ref "SW1") (pin "20") (pinfunction "20_20") (pintype "passive"))
      (node (ref "U1") (pin "9") (pinfunction "CHAN0_9") (pintype "bidirectional"))
    )
    (net (code "105") (name "Net-(U1-CHAN1)") (class "Default")
      (node (ref "SW1") (pin "19") (pinfunction "19_19") (pintype "passive"))
      (node (ref "U1") (pin "8") (pinfunction "CHAN1_8") (pintype "bidirectional"))
    )
    (net (code "106") (name "Net-(U1-CHAN2)") (class "Default")
      (node (ref "SW1") (pin "18") (pinfunction "18_18") (pintype "passive"))
      (node (ref "U1") (pin "7") (pinfunction "CHAN2_7") (pintype "bidirectional"))
    )
    (net (code "107") (name "Net-(U1-CHAN3)") (class "Default")
      (node (ref "SW1") (pin "17") (pinfunction "17_17") (pintype "passive"))
      (node (ref "U1") (pin "6") (pinfunction "CHAN3_6") (pintype "bidirectional"))
    )
    (net (code "108") (name "Net-(U1-CHAN4)") (class "Default")
      (node (ref "SW1") (pin "16") (pinfunction "16_16") (pintype "passive"))
      (node (ref "U1") (pin "5") (pinfunction "CHAN4_5") (pintype "bidirectional"))
    )
    (net (code "109") (name "Net-(U1-CHAN5)") (class "Default")
      (node (ref "SW1") (pin "15") (pinfunction "15_15") (pintype "passive"))
      (node (ref "U1") (pin "4") (pinfunction "CHAN5_4") (pintype "bidirectional"))
    )
    (net (code "110") (name "Net-(U1-CHAN6)") (class "Default")
      (node (ref "SW1") (pin "14") (pinfunction "14_14") (pintype "passive"))
      (node (ref "U1") (pin "3") (pinfunction "CHAN6_3") (pintype "bidirectional"))
    )
    (net (code "111") (name "Net-(U1-CHAN7)") (class "Default")
      (node (ref "SW1") (pin "13") (pinfunction "13_13") (pintype "passive"))
      (node (ref "U1") (pin "2") (pinfunction "CHAN7_2") (pintype "bidirectional"))
    )
    (net (code "112") (name "Net-(U1-CHAN8)") (class "Default")
      (node (ref "SW1") (pin "12") (pinfunction "12_12") (pintype "passive"))
      (node (ref "U1") (pin "23") (pinfunction "CHAN8_23") (pintype "bidirectional"))
    )
    (net (code "113") (name "Net-(U1-CHAN9)") (class "Default")
      (node (ref "SW1") (pin "11") (pinfunction "11_11") (pintype "passive"))
      (node (ref "U1") (pin "22") (pinfunction "CHAN9_22") (pintype "bidirectional"))
    )
    (net (code "114") (name "REG_5V") (class "Default")
      (node (ref "C15") (pin "+") (pinfunction "+_+") (pintype "passive"))
      (node (ref "S1") (pin "6") (pinfunction "6_6") (pintype "bidirectional"))
      (node (ref "U$2") (pin "CATHODE") (pinfunction "CATHODE_CATHODE") (pintype "bidirectional"))
      (node (ref "U$4") (pin "4") (pinfunction "GND_4") (pintype "input"))
    )
    (net (code "115") (name "S_SCL") (class "Default")
      (node (ref "CONN02") (pin "10") (pinfunction "10_10") (pintype "bidirectional"))
      (node (ref "U$1") (pin "29") (pinfunction "29/A18/SCL1_29") (pintype "bidirectional"))
    )
    (net (code "116") (name "S_SDA") (class "Default")
      (node (ref "CONN02") (pin "9") (pinfunction "9_9") (pintype "bidirectional"))
      (node (ref "U$1") (pin "30") (pinfunction "30/A19/SDA1_30") (pintype "bidirectional"))
    )
    (net (code "117") (name "S_SEN_01") (class "Default")
      (node (ref "CONN02") (pin "8") (pinfunction "8_8") (pintype "bidirectional"))
      (node (ref "U$1") (pin "A12") (pinfunction "A12_A12") (pintype "bidirectional"))
    )
    (net (code "118") (name "VBAT") (class "Default")
      (node (ref "U$1") (pin "VBAT") (pinfunction "VBAT_VBAT") (pintype "power_in"))
    )
    (net (code "119") (name "VCC1") (class "Default")
      (node (ref "J3") (pin "5") (pinfunction "5_5") (pintype "passive"))
    )
    (net (code "120") (name "VCC2") (class "Default")
      (node (ref "J4") (pin "5") (pinfunction "5_5") (pintype "passive"))
    )
    (net (code "121") (name "VCC_5V") (class "Default")
      (node (ref "C2") (pin "1") (pinfunction "P$1_1") (pintype "passive"))
      (node (ref "CONN01") (pin "11") (pinfunction "11_11") (pintype "bidirectional"))
      (node (ref "LED1") (pin "1-VDD") (pinfunction "VDD_1-VDD") (pintype "power_in"))
      (node (ref "MOTOR_01") (pin "FAULT") (pinfunction "FAULT_FAULT") (pintype "bidirectional"))
      (node (ref "MOTOR_02") (pin "FAULT") (pinfunction "FAULT_FAULT") (pintype "bidirectional"))
      (node (ref "MOTOR_03") (pin "FAULT") (pinfunction "FAULT_FAULT") (pintype "bidirectional"))
      (node (ref "MOTOR_04") (pin "FAULT") (pinfunction "FAULT_FAULT") (pintype "bidirectional"))
      (node (ref "MOTOR_05") (pin "FAULT") (pinfunction "FAULT_FAULT") (pintype "bidirectional"))
      (node (ref "MOTOR_06") (pin "FAULT") (pinfunction "FAULT_FAULT") (pintype "bidirectional"))
      (node (ref "MOTOR_07") (pin "FAULT") (pinfunction "FAULT_FAULT") (pintype "bidirectional"))
      (node (ref "MOTOR_08") (pin "FAULT") (pinfunction "FAULT_FAULT") (pintype "bidirectional"))
      (node (ref "POWER_LED_RES1") (pin "2") (pinfunction "2_2") (pintype "passive"))
      (node (ref "S1") (pin "3") (pinfunction "3_3") (pintype "bidirectional"))
      (node (ref "U$1") (pin "VIN") (pinfunction "VIN_VIN") (pintype "power_in"))
    )
    (net (code "122") (name "VCC_IN") (class "Default")
      (node (ref "INPUT_POWER_1") (pin "VCC_01") (pinfunction "VCC_01_VCC_01") (pintype "bidirectional"))
      (node (ref "INPUT_POWER_1") (pin "VCC_02") (pinfunction "VCC_02_VCC_02") (pintype "bidirectional"))
    )
    (net (code "123") (name "VCC_M") (class "Default")
      (node (ref "C10") (pin "+") (pinfunction "+_+") (pintype "passive"))
      (node (ref "C11") (pin "+") (pinfunction "+_+") (pintype "passive"))
      (node (ref "C4") (pin "+") (pinfunction "+_+") (pintype "passive"))
      (node (ref "C5") (pin "+") (pinfunction "+_+") (pintype "passive"))
      (node (ref "C6") (pin "+") (pinfunction "+_+") (pintype "passive"))
      (node (ref "C7") (pin "+") (pinfunction "+_+") (pintype "passive"))
      (node (ref "C8") (pin "+") (pinfunction "+_+") (pintype "passive"))
      (node (ref "C9") (pin "+") (pinfunction "+_+") (pintype "passive"))
      (node (ref "MOTOR_01") (pin "VM") (pinfunction "VM_VM") (pintype "bidirectional"))
      (node (ref "MOTOR_02") (pin "VM") (pinfunction "VM_VM") (pintype "bidirectional"))
      (node (ref "MOTOR_03") (pin "VM") (pinfunction "VM_VM") (pintype "bidirectional"))
      (node (ref "MOTOR_04") (pin "VM") (pinfunction "VM_VM") (pintype "bidirectional"))
      (node (ref "MOTOR_05") (pin "VM") (pinfunction "VM_VM") (pintype "bidirectional"))
      (node (ref "MOTOR_06") (pin "VM") (pinfunction "VM_VM") (pintype "bidirectional"))
      (node (ref "MOTOR_07") (pin "VM") (pinfunction "VM_VM") (pintype "bidirectional"))
      (node (ref "MOTOR_08") (pin "VM") (pinfunction "VM_VM") (pintype "bidirectional"))
      (node (ref "POWER_LED_RES") (pin "2") (pinfunction "2_2") (pintype "passive"))
      (node (ref "POWER_M") (pin "1") (pinfunction "1_1") (pintype "passive"))
    )
    (net (code "124") (name "VCC_MCU") (class "Default")
      (node (ref "C12") (pin "1") (pinfunction "P$1_1") (pintype "passive"))
      (node (ref "D1") (pin "C") (pinfunction "C_C") (pintype "passive"))
      (node (ref "POWER_MCU") (pin "1") (pinfunction "1_1") (pintype "passive"))
      (node (ref "U$2") (pin "ANODE") (pinfunction "ANODE_ANODE") (pintype "bidirectional"))
      (node (ref "U$4") (pin "3") (pinfunction "OUT_3") (pintype "passive"))
    )
    (net (code "125") (name "VUSB") (class "Default")
      (node (ref "U$1") (pin "VUSB") (pinfunction "VUSB_VUSB") (pintype "power_in"))
    )
    (net (code "126") (name "unconnected-(J3-Pad10)") (class "Default")
      (node (ref "J3") (pin "10") (pinfunction "10_10") (pintype "passive"))
    )
    (net (code "127") (name "unconnected-(J4-Pad10)") (class "Default")
      (node (ref "J4") (pin "10") (pinfunction "10_10") (pintype "passive"))
    )
    (net (code "128") (name "unconnected-(LED1-DO-Pad2-DOUT)") (class "Default")
      (node (ref "LED1") (pin "2-DOUT") (pinfunction "DO_2-DOUT") (pintype "output"))
    )
    (net (code "129") (name "unconnected-(MOTOR_01-Pad1)") (class "Default")
      (node (ref "MOTOR_01") (pin "1") (pinfunction "1_1") (pintype "bidirectional"))
    )
    (net (code "130") (name "unconnected-(MOTOR_01-Pad2)") (class "Default")
      (node (ref "MOTOR_01") (pin "2") (pinfunction "2_2") (pintype "bidirectional"))
    )
    (net (code "131") (name "unconnected-(MOTOR_01-PadSTBY)") (class "Default")
      (node (ref "MOTOR_01") (pin "STBY") (pinfunction "STBY_STBY") (pintype "bidirectional"))
    )
    (net (code "132") (name "unconnected-(MOTOR_02-Pad1)") (class "Default")
      (node (ref "MOTOR_02") (pin "1") (pinfunction "1_1") (pintype "bidirectional"))
    )
    (net (code "133") (name "unconnected-(MOTOR_02-Pad2)") (class "Default")
      (node (ref "MOTOR_02") (pin "2") (pinfunction "2_2") (pintype "bidirectional"))
    )
    (net (code "134") (name "unconnected-(MOTOR_02-PadSTBY)") (class "Default")
      (node (ref "MOTOR_02") (pin "STBY") (pinfunction "STBY_STBY") (pintype "bidirectional"))
    )
    (net (code "135") (name "unconnected-(MOTOR_03-Pad1)") (class "Default")
      (node (ref "MOTOR_03") (pin "1") (pinfunction "1_1") (pintype "bidirectional"))
    )
    (net (code "136") (name "unconnected-(MOTOR_03-Pad2)") (class "Default")
      (node (ref "MOTOR_03") (pin "2") (pinfunction "2_2") (pintype "bidirectional"))
    )
    (net (code "137") (name "unconnected-(MOTOR_03-PadSTBY)") (class "Default")
      (node (ref "MOTOR_03") (pin "STBY") (pinfunction "STBY_STBY") (pintype "bidirectional"))
    )
    (net (code "138") (name "unconnected-(MOTOR_04-Pad1)") (class "Default")
      (node (ref "MOTOR_04") (pin "1") (pinfunction "1_1") (pintype "bidirectional"))
    )
    (net (code "139") (name "unconnected-(MOTOR_04-Pad2)") (class "Default")
      (node (ref "MOTOR_04") (pin "2") (pinfunction "2_2") (pintype "bidirectional"))
    )
    (net (code "140") (name "unconnected-(MOTOR_04-PadSTBY)") (class "Default")
      (node (ref "MOTOR_04") (pin "STBY") (pinfunction "STBY_STBY") (pintype "bidirectional"))
    )
    (net (code "141") (name "unconnected-(MOTOR_05-Pad1)") (class "Default")
      (node (ref "MOTOR_05") (pin "1") (pinfunction "1_1") (pintype "bidirectional"))
    )
    (net (code "142") (name "unconnected-(MOTOR_05-Pad2)") (class "Default")
      (node (ref "MOTOR_05") (pin "2") (pinfunction "2_2") (pintype "bidirectional"))
    )
    (net (code "143") (name "unconnected-(MOTOR_05-PadSTBY)") (class "Default")
      (node (ref "MOTOR_05") (pin "STBY") (pinfunction "STBY_STBY") (pintype "bidirectional"))
    )
    (net (code "144") (name "unconnected-(MOTOR_06-Pad1)") (class "Default")
      (node (ref "MOTOR_06") (pin "1") (pinfunction "1_1") (pintype "bidirectional"))
    )
    (net (code "145") (name "unconnected-(MOTOR_06-Pad2)") (class "Default")
      (node (ref "MOTOR_06") (pin "2") (pinfunction "2_2") (pintype "bidirectional"))
    )
    (net (code "146") (name "unconnected-(MOTOR_06-PadSTBY)") (class "Default")
      (node (ref "MOTOR_06") (pin "STBY") (pinfunction "STBY_STBY") (pintype "bidirectional"))
    )
    (net (code "147") (name "unconnected-(MOTOR_07-Pad1)") (class "Default")
      (node (ref "MOTOR_07") (pin "1") (pinfunction "1_1") (pintype "bidirectional"))
    )
    (net (code "148") (name "unconnected-(MOTOR_07-Pad2)") (class "Default")
      (node (ref "MOTOR_07") (pin "2") (pinfunction "2_2") (pintype "bidirectional"))
    )
    (net (code "149") (name "unconnected-(MOTOR_07-PadSTBY)") (class "Default")
      (node (ref "MOTOR_07") (pin "STBY") (pinfunction "STBY_STBY") (pintype "bidirectional"))
    )
    (net (code "150") (name "unconnected-(MOTOR_08-Pad1)") (class "Default")
      (node (ref "MOTOR_08") (pin "1") (pinfunction "1_1") (pintype "bidirectional"))
    )
    (net (code "151") (name "unconnected-(MOTOR_08-Pad2)") (class "Default")
      (node (ref "MOTOR_08") (pin "2") (pinfunction "2_2") (pintype "bidirectional"))
    )
    (net (code "152") (name "unconnected-(MOTOR_08-PadSTBY)") (class "Default")
      (node (ref "MOTOR_08") (pin "STBY") (pinfunction "STBY_STBY") (pintype "bidirectional"))
    )
    (net (code "153") (name "unconnected-(S1-Pad1)") (class "Default")
      (node (ref "S1") (pin "1") (pinfunction "1_1") (pintype "bidirectional"))
    )
    (net (code "154") (name "unconnected-(S1-Pad2)") (class "Default")
      (node (ref "S1") (pin "2") (pinfunction "2_2") (pintype "bidirectional"))
    )
    (net (code "155") (name "unconnected-(S1-Pad4)") (class "Default")
      (node (ref "S1") (pin "4") (pinfunction "4_4") (pintype "bidirectional"))
    )
    (net (code "156") (name "unconnected-(S1-Pad5)") (class "Default")
      (node (ref "S1") (pin "5") (pinfunction "5_5") (pintype "bidirectional"))
    )
    (net (code "157") (name "unconnected-(TCAN1042-NC-Pad5)") (class "Default")
      (node (ref "TCAN1042") (pin "5") (pinfunction "NC_5") (pintype "passive"))
    )
    (net (code "158") (name "unconnected-(U$1-0{slash}RX1{slash}T-Pad0)") (class "Default")
      (node (ref "U$1") (pin "0") (pinfunction "0/RX1/T_0") (pintype "bidirectional"))
    )
    (net (code "159") (name "unconnected-(U$1-1{slash}TX1{slash}T-Pad1)") (class "Default")
      (node (ref "U$1") (pin "1") (pinfunction "1/TX1/T_1") (pintype "bidirectional"))
    )
    (net (code "160") (name "unconnected-(U$1-13{slash}SCK{slash}LED-Pad13)") (class "Default")
      (node (ref "U$1") (pin "13") (pinfunction "13/SCK/LED_13") (pintype "bidirectional"))
    )
    (net (code "161") (name "unconnected-(U$1-A14{slash}DAC-PadRESET{slash}DAC)") (class "Default")
      (node (ref "U$1") (pin "RESET/DAC") (pinfunction "A14/DAC_RESET/DAC") (pintype "bidirectional"))
    )
    (net (code "162") (name "unconnected-(U$1-PadA10)") (class "Default")
      (node (ref "U$1") (pin "A10") (pinfunction "A10_A10") (pintype "bidirectional"))
    )
    (net (code "163") (name "unconnected-(U$1-PadA11)") (class "Default")
      (node (ref "U$1") (pin "A11") (pinfunction "A11_A11") (pintype "bidirectional"))
    )
    (net (code "164") (name "unconnected-(U$1-PadPGM)") (class "Default")
      (node (ref "U$1") (pin "PGM") (pinfunction "PGM_PGM") (pintype "bidirectional"))
    )
    (net (code "165") (name "unconnected-(U$2-NC-PadNC@1)") (class "Default")
      (node (ref "U$2") (pin "NC@1") (pinfunction "NC_NC@1") (pintype "no_connect"))
    )
    (net (code "166") (name "unconnected-(U$2-NC-PadNC@2)") (class "Default")
      (node (ref "U$2") (pin "NC@2") (pinfunction "NC_NC@2") (pintype "no_connect"))
    )
    (net (code "167") (name "unconnected-(U1-CHAN10-Pad21)") (class "Default")
      (node (ref "U1") (pin "21") (pinfunction "CHAN10_21") (pintype "bidirectional"))
    )
    (net (code "168") (name "unconnected-(U1-CHAN11-Pad20)") (class "Default")
      (node (ref "U1") (pin "20") (pinfunction "CHAN11_20") (pintype "bidirectional"))
    )
    (net (code "169") (name "unconnected-(U1-CHAN12-Pad19)") (class "Default")
      (node (ref "U1") (pin "19") (pinfunction "CHAN12_19") (pintype "bidirectional"))
    )
    (net (code "170") (name "unconnected-(U1-CHAN13-Pad18)") (class "Default")
      (node (ref "U1") (pin "18") (pinfunction "CHAN13_18") (pintype "bidirectional"))
    )
    (net (code "171") (name "unconnected-(U1-CHAN14-Pad17)") (class "Default")
      (node (ref "U1") (pin "17") (pinfunction "CHAN14_17") (pintype "bidirectional"))
    )
    (net (code "172") (name "unconnected-(U1-CHAN15-Pad16)") (class "Default")
      (node (ref "U1") (pin "16") (pinfunction "CHAN15_16") (pintype "bidirectional"))
    )
  )
)
